# Counter_Switch.net
KiCad netlist of a schematic drawn in Altium Designer
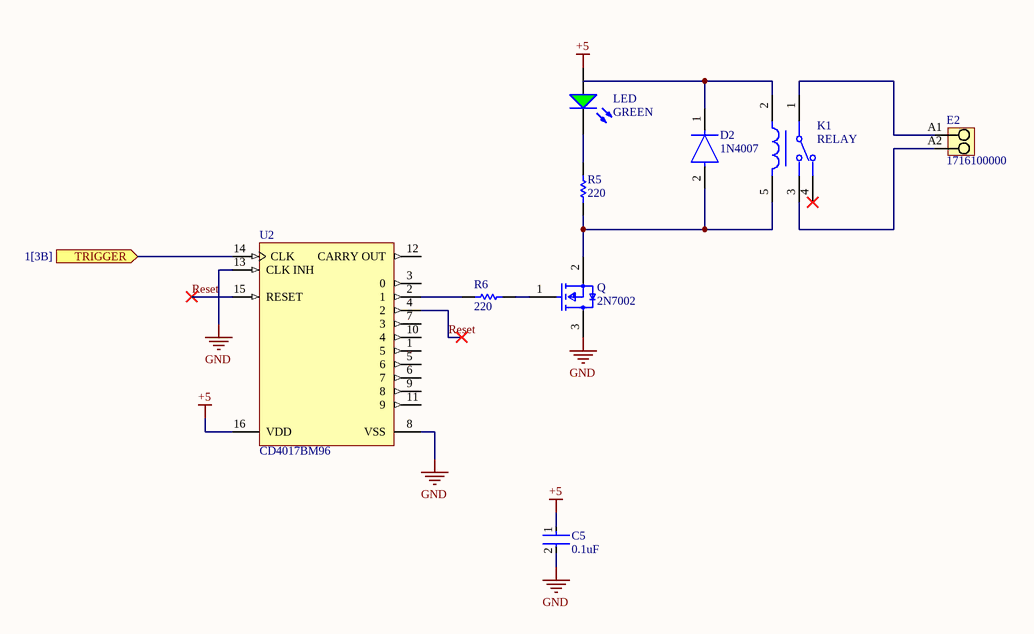
[diagram p0: Counter Switch.SchDoc]

(export (version "E")
  (design (tool "Eeschema 10.0.6"))
  (components
    (comp (ref "C5")
      (value "0.1uF")
      (footprint "FP-GRM21B-0_1-MFG")
      (description "Chip Multilayer Ceramic Capacitors for General Purpose, 0805, 0.10uF, U2J, -750ppm/°C, 5%, 10V")
      (fields (field (name "TOLERANCE") "5%"))
      (libsource (lib "MDL") (part "CAP 0.1uF 10V 0805"))
    )
    (comp (ref "D2")
      (value "1N4007")
      (footprint "FP-1N4007-MFG")
      (description "Rectifier diode 1000 V 1 A DO-41, ,")
      (fields
        (field (name "MANUFACTURER") "Diotec")
        (field (name "OCTOPART") "https://octopart.com/1n4007-diotec-4040411")
      )
      (libsource (lib "MDL") (part "D2 Diode 1N4007"))
    )
    (comp (ref "E2")
      (value "1716100000")
      (footprint "LM_5_08_180_02")
      (description "OMNIMATE Signal - series LM")
      (fields (field (name "MANUFACTURER") "Weidmueller"))
      (libsource (lib "MDL") (part "Term Block 2Pos 14AWG"))
    )
    (comp (ref "K1")
      (value "RELAY")
      (footprint "FP-G5LE-1-E-36-DC5-MFG")
      (description "RELAY GEN PURPOSE SPDT 16A 5V")
      (libsource (lib "MDL") (part "RELAY SPDT 5V"))
    )
    (comp (ref "LED")
      (value "GREEN")
      (footprint "KING-WP7113SGD_V")
      (description "LED Green, 62.5 mW, 25 mA, -40 to 85 degC, 2-Pin THD, RoHS, Bulk")
      (fields (field (name "MANUFACTURER") "Kingbright"))
      (libsource (lib "MDL") (part "LED Green 5mm"))
    )
    (comp (ref "Q")
      (value "2N7002")
      (footprint "FP-PG-SOT23-3-IPC_B")
      (description "MOSFET N-CH 60V 0.3A SOT23")
      (libsource (lib "MDL") (part "MOSFET 2N7002 SMT"))
    )
    (comp (ref "R5")
      (value "220")
      (footprint "RESC3216X60X45ML10T20")
      (fields (field (name "MANUFACTURER") "Vishay Dale") (field (name "PART NUMBER") "CRCW1206220RFKEA"))
      (libsource (lib "MDL") (part "Res 220 Ohm 1/4W SMT"))
    )
    (comp (ref "R6")
      (value "220")
      (footprint "RESC3216X60X45ML10T20")
      (fields (field (name "MANUFACTURER") "Vishay Dale") (field (name "PART NUMBER") "CRCW1206220RFKEA"))
      (libsource (lib "MDL") (part "Res 220 Ohm 1/4W SMT"))
    )
    (comp (ref "U2")
      (value "CD4017BM96")
      (footprint "D0016A_N")
      (description "CMOS Decade Counter with 10 Decoded Outputs, D0016A, LARGE T&R")
      (fields
        (field (name "GENERIC PART NUMBER") "CD4017B")
        (field (name "MANUFACTURER") "Texas Instruments")
      )
      (libsource (lib "MDL") (part "IC CD4017"))
    )
  )
  (nets
    (net (code "1") (name "+5") (class "Default")
      (node (ref "C5") (pin "1") (pinfunction "1_1") (pintype "passive"))
      (node (ref "LED") (pin "1") (pinfunction "A_1") (pintype "passive"))
      (node (ref "U2") (pin "16") (pinfunction "VDD_16") (pintype "power_in"))
    )
    (net (code "2") (name "/Reset") (class "Default")
      (node (ref "U2") (pin "15") (pinfunction "RESET_15") (pintype "input"))
      (node (ref "U2") (pin "4") (pinfunction "2_4") (pintype "output"))
    )
    (net (code "3") (name "/TRIGGER") (class "Default")
      (node (ref "U2") (pin "14") (pinfunction "CLK_14") (pintype "input"))
    )
    (net (code "4") (name "GND") (class "Default")
      (node (ref "C5") (pin "2") (pinfunction "2_2") (pintype "passive"))
      (node (ref "Q") (pin "3") (pinfunction "drain_3") (pintype "passive"))
      (node (ref "U2") (pin "13") (pinfunction "CLK_INH_13") (pintype "input"))
      (node (ref "U2") (pin "8") (pinfunction "VSS_8") (pintype "power_in"))
    )
    (net (code "5") (name "Net-(D2-A)") (class "Default")
      (node (ref "D2") (pin "2") (pinfunction "A_2") (pintype "passive"))
      (node (ref "K1") (pin "5") (pinfunction "5_5") (pintype "passive"))
      (node (ref "Q") (pin "2") (pinfunction "source_2") (pintype "passive"))
      (node (ref "R5") (pin "1") (pinfunction "1_1") (pintype "passive"))
    )
    (net (code "6") (name "Net-(D2-C)") (class "Default")
      (node (ref "D2") (pin "1") (pinfunction "C_1") (pintype "passive"))
      (node (ref "K1") (pin "2") (pinfunction "2_2") (pintype "passive"))
    )
    (net (code "7") (name "Net-(E2-PadA1)") (class "Default")
      (node (ref "E2") (pin "A1") (pinfunction "A1_A1") (pintype "passive"))
      (node (ref "K1") (pin "1") (pinfunction "1_1") (pintype "passive"))
    )
    (net (code "8") (name "Net-(E2-PadA2)") (class "Default")
      (node (ref "E2") (pin "A2") (pinfunction "A2_A2") (pintype "passive"))
      (node (ref "K1") (pin "3") (pinfunction "3_3") (pintype "passive"))
    )
    (net (code "9") (name "Net-(LED-K)") (class "Default")
      (node (ref "LED") (pin "2") (pinfunction "K_2") (pintype "passive"))
      (node (ref "R5") (pin "2") (pinfunction "2_2") (pintype "passive"))
    )
    (net (code "10") (name "Net-(Q-gate)") (class "Default")
      (node (ref "Q") (pin "1") (pinfunction "gate_1") (pintype "passive"))
      (node (ref "R6") (pin "2") (pinfunction "2_2") (pintype "passive"))
    )
    (net (code "11") (name "Net-(U2-1)") (class "Default")
      (node (ref "R6") (pin "1") (pinfunction "1_1") (pintype "passive"))
      (node (ref "U2") (pin "2") (pinfunction "1_2") (pintype "output"))
    )
    (net (code "12") (name "unconnected-(K1-Pad4)") (class "Default")
      (node (ref "K1") (pin "4") (pinfunction "4_4") (pintype "passive+no_connect"))
    )
    (net (code "13") (name "unconnected-(U2-0-Pad3)") (class "Default")
      (node (ref "U2") (pin "3") (pinfunction "0_3") (pintype "output"))
    )
    (net (code "14") (name "unconnected-(U2-3-Pad7)") (class "Default")
      (node (ref "U2") (pin "7") (pinfunction "3_7") (pintype "output"))
    )
    (net (code "15") (name "unconnected-(U2-4-Pad10)") (class "Default")
      (node (ref "U2") (pin "10") (pinfunction "4_10") (pintype "output"))
    )
    (net (code "16") (name "unconnected-(U2-5-Pad1)") (class "Default")
      (node (ref "U2") (pin "1") (pinfunction "5_1") (pintype "output"))
    )
    (net (code "17") (name "unconnected-(U2-6-Pad5)") (class "Default")
      (node (ref "U2") (pin "5") (pinfunction "6_5") (pintype "output"))
    )
    (net (code "18") (name "unconnected-(U2-7-Pad6)") (class "Default")
      (node (ref "U2") (pin "6") (pinfunction "7_6") (pintype "output"))
    )
    (net (code "19") (name "unconnected-(U2-8-Pad9)") (class "Default")
      (node (ref "U2") (pin "9") (pinfunction "8_9") (pintype "output"))
    )
    (net (code "20") (name "unconnected-(U2-9-Pad11)") (class "Default")
      (node (ref "U2") (pin "11") (pinfunction "9_11") (pintype "output"))
    )
    (net (code "21") (name "unconnected-(U2-CARRY_OUT-Pad12)") (class "Default")
      (node (ref "U2") (pin "12") (pinfunction "CARRY_OUT_12") (pintype "output"))
    )
  )
)
